# Battery_Measurement.net
KiCad netlist of a schematic drawn in Altium Designer
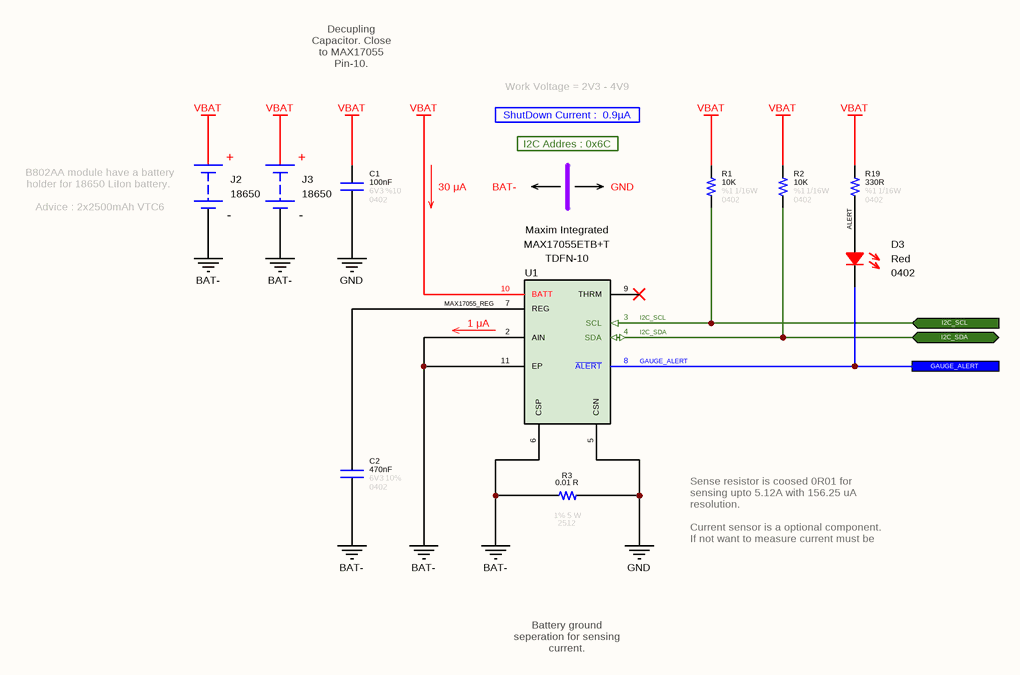
[diagram p0: Battery Measurement.SchDoc]

(export (version "E")
  (design (tool "Eeschema 10.0.6"))
  (components
    (comp (ref "C1")
      (value "100nF")
      (footprint "CAPACITOR_0402")
      (description "Capacitor - 100nF [0402-6V3] (Ceramic)")
      (fields
        (field (name "MANUFACTURER PART NUMBER") "04026D104KAT4A")
        (field (name "TOLERANCE") "%10")
        (field (name "VOLTAGE") "6V3")
        (field (name "CASE") "0402")
        (field (name "Comment") "Capacitor - 100nF [0402] (Ceramic)")
      )
      (libsource (lib "P101DA_Library") (part "Capacitor - 100nF [0402-6V3]"))
    )
    (comp (ref "C2")
      (value "470nF")
      (footprint "CAPACITOR_0402")
      (description "Multilayer Ceramic Capacitors - SMD - 6.3V 470nF X7R 0402 10%")
      (fields
        (field (name "MANUFACTURER PART NUMBER") "04026C474KAT2A")
        (field (name "TOLERANCE") "10%")
        (field (name "CASE") "0402")
        (field (name "VOLTAGE") "6V3")
        (field (name "Comment") "Capacitor - 470nF [0402] (Ceramic)")
      )
      (libsource (lib "P101DA_Library") (part "Capacitor - 470 nF [0402-6V3]"))
    )
    (comp (ref "D3")
      (value "SMD LED (Red)")
      (footprint "LED_0402")
      (description "Standard LEDs - SMD MINI-MOLD ULTRA COMPACT RED")
      (fields
        (field (name "MANUFACTURER PART NUMBER") "SML-P12VTT86R")
        (field (name "CASE") "0402")
        (field (name "COLOR") "Red")
      )
      (libsource (lib "P101DA_Library") (part "Diode - LED (0402-Red)"))
    )
    (comp (ref "J2")
      (value "54")
      (footprint "BATTERY_HOLDER - Bat")
      (description "BATTERY CONTACT CLP 18650 PC PIN")
      (fields (field (name "BATTERY SIZE") "18650"))
      (libsource (lib "P101DA_Library") (part "Connector - 18650 Battery Holder"))
    )
    (comp (ref "J3")
      (value "54")
      (footprint "BATTERY_HOLDER - Bat")
      (description "BATTERY CONTACT CLP 18650 PC PIN")
      (fields (field (name "BATTERY SIZE") "18650"))
      (libsource (lib "P101DA_Library") (part "Connector - 18650 Battery Holder"))
    )
    (comp (ref "R1")
      (value "10K")
      (footprint "RESISTOR_0402")
      (description "Thick Film Resistors - SMD 1/16 W 10 KOhm 1%")
      (fields
        (field (name "MANUFACTURER PART NUMBER") "CRCW040210K0FKED")
        (field (name "TOLERANCE") "%1")
        (field (name "CASE") "0402")
        (field (name "POWER") "1/16W")
        (field (name "Comment") "10K - 0402 - %1 - 1/16W")
      )
      (libsource (lib "P101DA_Library") (part "Resistor - 10K [0402]"))
    )
    (comp (ref "R2")
      (value "10K")
      (footprint "RESISTOR_0402")
      (description "Thick Film Resistors - SMD 1/16 W 10 KOhm 1%")
      (fields
        (field (name "MANUFACTURER PART NUMBER") "CRCW040210K0FKED")
        (field (name "TOLERANCE") "%1")
        (field (name "CASE") "0402")
        (field (name "POWER") "1/16W")
        (field (name "Comment") "10K - 0402 - %1 - 1/16W")
      )
      (libsource (lib "P101DA_Library") (part "Resistor - 10K [0402]"))
    )
    (comp (ref "R3")
      (value "0.01 R")
      (footprint "RESISTOR_2512 SHUNT")
      (description "Shunt Resistors - SMD 5 W 0.01 Ohm 1%")
      (fields
        (field (name "MANUFACTURER PART NUMBER") "TLRH3APTTE10L0F")
        (field (name "TOLERANCE") "1%")
        (field (name "POWER") "5 W")
        (field (name "CASE") "2512")
        (field (name "Comment") "0R01 - 2512 - %1 - 5W")
      )
      (libsource (lib "P101DA_Library") (part "Resistor - 0R01 [2512]"))
    )
    (comp (ref "R19")
      (value "330R")
      (footprint "RESISTOR_0402")
      (description "Thick Film Resistors - SMD 1/16 W 330 Ohm 1%")
      (fields
        (field (name "MANUFACTURER PART NUMBER") "CRCW0402330RFKED")
        (field (name "CASE") "0402")
        (field (name "TOLERANCE") "%1")
        (field (name "POWER") "1/16W")
        (field (name "Comment") "330R - 0402 - %1 - 1/16W")
      )
      (libsource (lib "P101DA_Library") (part "Resistor - 330R [0402]"))
    )
    (comp (ref "U1")
      (value "MAX17055ETB+T")
      (footprint "TDFN-10")
      (description "IC FUEL GAUGE MODELGAUGE 10TDFN")
      (fields
        (field (name "MANUFACTURER NAME") "Maxim Integrated")
        (field (name "MANUFACTURER PART NUMBER") "MAX17055ETB+T")
        (field (name "CASE") "TDFN-10")
      )
      (libsource (lib "P101DA_Library") (part "IC - MAX17055"))
    )
  )
  (nets
    (net (code "1") (name "/ALERT") (class "Default")
      (node (ref "D3") (pin "2") (pinfunction "2_2") (pintype "passive"))
      (node (ref "R19") (pin "1") (pinfunction "1_1") (pintype "passive"))
    )
    (net (code "2") (name "/GAUGE_ALERT") (class "Default")
      (node (ref "D3") (pin "1") (pinfunction "1_1") (pintype "passive"))
      (node (ref "U1") (pin "8") (pinfunction "~{ALERT}_8") (pintype "passive"))
    )
    (net (code "3") (name "/I2C_SCL") (class "Default")
      (node (ref "R1") (pin "1") (pinfunction "1_1") (pintype "passive"))
      (node (ref "U1") (pin "3") (pinfunction "SCL_3") (pintype "input"))
    )
    (net (code "4") (name "/I2C_SDA") (class "Default")
      (node (ref "R2") (pin "1") (pinfunction "1_1") (pintype "passive"))
      (node (ref "U1") (pin "4") (pinfunction "SDA_4") (pintype "bidirectional"))
    )
    (net (code "5") (name "/MAX17055_REG") (class "Default")
      (node (ref "C2") (pin "2") (pinfunction "2_2") (pintype "passive"))
      (node (ref "U1") (pin "7") (pinfunction "REG_7") (pintype "passive"))
    )
    (net (code "6") (name "BAT-") (class "Default")
      (node (ref "C2") (pin "1") (pinfunction "1_1") (pintype "passive"))
      (node (ref "J2") (pin "2") (pinfunction "BAT-_2") (pintype "power_in"))
      (node (ref "J3") (pin "2") (pinfunction "BAT-_2") (pintype "power_in"))
      (node (ref "R3") (pin "2") (pinfunction "2_2") (pintype "passive"))
      (node (ref "U1") (pin "11") (pinfunction "EP_11") (pintype "passive"))
      (node (ref "U1") (pin "2") (pinfunction "AIN_2") (pintype "passive"))
      (node (ref "U1") (pin "6") (pinfunction "CSP_6") (pintype "power_in"))
    )
    (net (code "7") (name "GND") (class "Default")
      (node (ref "C1") (pin "1") (pinfunction "1_1") (pintype "passive"))
      (node (ref "R3") (pin "1") (pinfunction "1_1") (pintype "passive"))
      (node (ref "U1") (pin "5") (pinfunction "CSN_5") (pintype "power_in"))
    )
    (net (code "8") (name "VBAT") (class "Default")
      (node (ref "C1") (pin "2") (pinfunction "2_2") (pintype "passive"))
      (node (ref "J2") (pin "1") (pinfunction "BAT+_1") (pintype "power_in"))
      (node (ref "J3") (pin "1") (pinfunction "BAT+_1") (pintype "power_in"))
      (node (ref "R1") (pin "2") (pinfunction "2_2") (pintype "passive"))
      (node (ref "R19") (pin "2") (pinfunction "2_2") (pintype "passive"))
      (node (ref "R2") (pin "2") (pinfunction "2_2") (pintype "passive"))
      (node (ref "U1") (pin "10") (pinfunction "BATT_10") (pintype "power_in"))
    )
    (net (code "9") (name "unconnected-(U1-THRM-Pad9)") (class "Default")
      (node (ref "U1") (pin "9") (pinfunction "THRM_9") (pintype "passive+no_connect"))
    )
  )
)
